# Placa_ATMEL_2019_v2_4.net
KiCad netlist of a schematic drawn in EAGLE
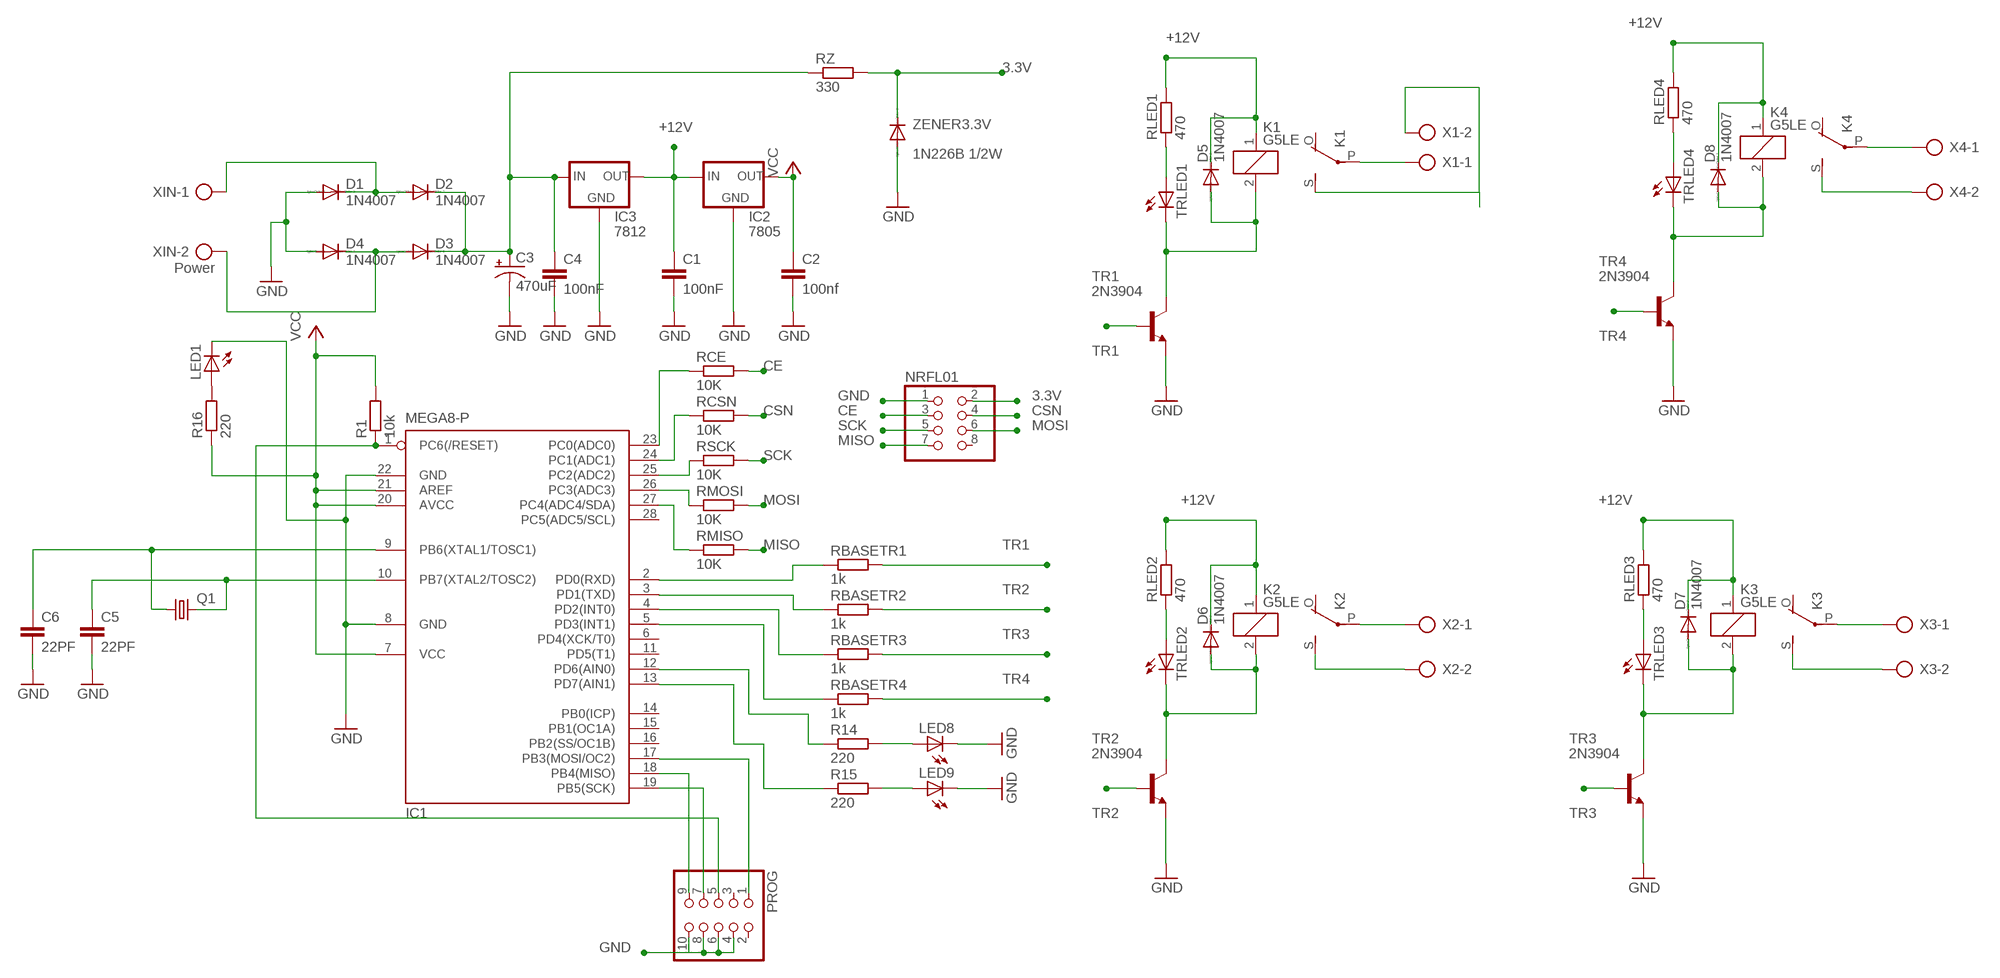
[diagram p0: schematic, sheet 1]

(export (version "E")
  (design (tool "Eeschema 10.0.6"))
  (components
    (comp (ref "C1")
      (value "100nF")
      (footprint "eagle-import:C050-025X075")
      (libsource (lib "eagle-import") (part "C-EU050-025X075"))
    )
    (comp (ref "C2")
      (value "100nf")
      (footprint "eagle-import:C050-025X075")
      (libsource (lib "eagle-import") (part "C-EU050-025X075"))
    )
    (comp (ref "C3")
      (value "470uF")
      (footprint "eagle-import:E7,5-16")
      (libsource (lib "eagle-import") (part "CPOL-USE7.5-16"))
    )
    (comp (ref "C4")
      (value "100nF")
      (footprint "eagle-import:C050-025X075")
      (libsource (lib "eagle-import") (part "C-EU050-025X075"))
    )
    (comp (ref "C5")
      (value "22PF")
      (footprint "eagle-import:C050-024X044")
      (libsource (lib "eagle-import") (part "C-EU050-024X044"))
    )
    (comp (ref "C6")
      (value "22PF")
      (footprint "eagle-import:C050-024X044")
      (libsource (lib "eagle-import") (part "C-EU050-024X044"))
    )
    (comp (ref "D1")
      (value "1N4007")
      (footprint "eagle-import:DO41-10")
      (libsource (lib "eagle-import") (part "1N4004"))
    )
    (comp (ref "D2")
      (value "1N4007")
      (footprint "eagle-import:DO41-10")
      (libsource (lib "eagle-import") (part "1N4004"))
    )
    (comp (ref "D3")
      (value "1N4007")
      (footprint "eagle-import:DO41-10")
      (libsource (lib "eagle-import") (part "1N4004"))
    )
    (comp (ref "D4")
      (value "1N4007")
      (footprint "eagle-import:DO41-10")
      (libsource (lib "eagle-import") (part "1N4004"))
    )
    (comp (ref "D5")
      (value "1N4007")
      (footprint "eagle-import:DO41-10")
      (libsource (lib "eagle-import") (part "1N4004"))
    )
    (comp (ref "D6")
      (value "1N4007")
      (footprint "eagle-import:DO41-10")
      (libsource (lib "eagle-import") (part "1N4004"))
    )
    (comp (ref "D7")
      (value "1N4007")
      (footprint "eagle-import:DO41-10")
      (libsource (lib "eagle-import") (part "1N4004"))
    )
    (comp (ref "D8")
      (value "1N4007")
      (footprint "eagle-import:DO41-10")
      (libsource (lib "eagle-import") (part "1N4004"))
    )
    (comp (ref "IC1")
      (value "MEGA8-P")
      (footprint "eagle-import:DIL28-3")
      (libsource (lib "eagle-import") (part "MEGA8-P"))
    )
    (comp (ref "IC2")
      (value "7805")
      (footprint "eagle-import:78XXL")
      (libsource (lib "eagle-import") (part "78XXL"))
    )
    (comp (ref "IC3")
      (value "7812")
      (footprint "eagle-import:78XXL")
      (libsource (lib "eagle-import") (part "78XXL"))
    )
    (comp (ref "K1")
      (value "G5LE")
      (footprint "eagle-import:G5LE")
      (libsource (lib "eagle-import") (part "G5LE"))
    )
    (comp (ref "K2")
      (value "G5LE")
      (footprint "eagle-import:G5LE")
      (libsource (lib "eagle-import") (part "G5LE"))
    )
    (comp (ref "K3")
      (value "G5LE")
      (footprint "eagle-import:G5LE")
      (libsource (lib "eagle-import") (part "G5LE"))
    )
    (comp (ref "K4")
      (value "G5LE")
      (footprint "eagle-import:G5LE")
      (libsource (lib "eagle-import") (part "G5LE"))
    )
    (comp (ref "LED1")
      (value "LED5MM")
      (footprint "eagle-import:LED5MM")
      (libsource (lib "eagle-import") (part "LED5MM"))
    )
    (comp (ref "LED8")
      (value "LED5MM")
      (footprint "eagle-import:LED5MM")
      (libsource (lib "eagle-import") (part "LED5MM"))
    )
    (comp (ref "LED9")
      (value "LED5MM")
      (footprint "eagle-import:LED5MM")
      (libsource (lib "eagle-import") (part "LED5MM"))
    )
    (comp (ref "NRFL01")
      (value "PINHD-2X4")
      (footprint "eagle-import:2X04")
      (libsource (lib "eagle-import") (part "PINHD-2X4"))
    )
    (comp (ref "PROG")
      (value "PINHD-2X5")
      (footprint "eagle-import:2X05")
      (libsource (lib "eagle-import") (part "PINHD-2X5"))
    )
    (comp (ref "Q1")
      (value "CRYSTALHC49S")
      (footprint "eagle-import:HC49_S")
      (libsource (lib "eagle-import") (part "CRYSTALHC49S"))
    )
    (comp (ref "R1")
      (value "10k")
      (footprint "eagle-import:0207_10")
      (libsource (lib "eagle-import") (part "R-EU_0207/10"))
    )
    (comp (ref "R14")
      (value "220")
      (footprint "eagle-import:0207_10")
      (libsource (lib "eagle-import") (part "R-EU_0207/10"))
    )
    (comp (ref "R15")
      (value "220")
      (footprint "eagle-import:0207_10")
      (libsource (lib "eagle-import") (part "R-EU_0207/10"))
    )
    (comp (ref "R16")
      (value "220")
      (footprint "eagle-import:0309_10")
      (libsource (lib "eagle-import") (part "R-EU_0309/10"))
    )
    (comp (ref "RBASETR1")
      (value "1k")
      (footprint "eagle-import:0207_10")
      (libsource (lib "eagle-import") (part "R-EU_0207/10"))
    )
    (comp (ref "RBASETR2")
      (value "1k")
      (footprint "eagle-import:0207_10")
      (libsource (lib "eagle-import") (part "R-EU_0207/10"))
    )
    (comp (ref "RBASETR3")
      (value "1k")
      (footprint "eagle-import:0204_7")
      (libsource (lib "eagle-import") (part "R-EU_0204/7"))
    )
    (comp (ref "RBASETR4")
      (value "1k")
      (footprint "eagle-import:0207_15")
      (libsource (lib "eagle-import") (part "R-EU_0207/15"))
    )
    (comp (ref "RCE")
      (value "10K")
      (footprint "eagle-import:0207_10")
      (libsource (lib "eagle-import") (part "R-EU_0207/10"))
    )
    (comp (ref "RCSN")
      (value "10K")
      (footprint "eagle-import:0207_10")
      (libsource (lib "eagle-import") (part "R-EU_0207/10"))
    )
    (comp (ref "RLED1")
      (value "470")
      (footprint "eagle-import:0207_10")
      (libsource (lib "eagle-import") (part "R-EU_0207/10"))
    )
    (comp (ref "RLED2")
      (value "470")
      (footprint "eagle-import:0207_10")
      (libsource (lib "eagle-import") (part "R-EU_0207/10"))
    )
    (comp (ref "RLED3")
      (value "470")
      (footprint "eagle-import:0207_10")
      (libsource (lib "eagle-import") (part "R-EU_0207/10"))
    )
    (comp (ref "RLED4")
      (value "470")
      (footprint "eagle-import:0207_10")
      (libsource (lib "eagle-import") (part "R-EU_0207/10"))
    )
    (comp (ref "RMISO")
      (value "10K")
      (footprint "eagle-import:0207_10")
      (libsource (lib "eagle-import") (part "R-EU_0207/10"))
    )
    (comp (ref "RMOSI")
      (value "10K")
      (footprint "eagle-import:0207_10")
      (libsource (lib "eagle-import") (part "R-EU_0207/10"))
    )
    (comp (ref "RSCK")
      (value "10K")
      (footprint "eagle-import:0207_10")
      (libsource (lib "eagle-import") (part "R-EU_0207/10"))
    )
    (comp (ref "RZ")
      (value "330")
      (footprint "eagle-import:0207_10")
      (libsource (lib "eagle-import") (part "R-EU_0207/10"))
    )
    (comp (ref "TR1")
      (value "2N3904")
      (footprint "eagle-import:TO92")
      (libsource (lib "eagle-import") (part "2N3904"))
    )
    (comp (ref "TR2")
      (value "2N3904")
      (footprint "eagle-import:TO92")
      (libsource (lib "eagle-import") (part "2N3904"))
    )
    (comp (ref "TR3")
      (value "2N3904")
      (footprint "eagle-import:TO92")
      (libsource (lib "eagle-import") (part "2N3904"))
    )
    (comp (ref "TR4")
      (value "2N3904")
      (footprint "eagle-import:TO92")
      (libsource (lib "eagle-import") (part "2N3904"))
    )
    (comp (ref "TRLED1")
      (value "LED5MM")
      (footprint "eagle-import:LED5MM")
      (libsource (lib "eagle-import") (part "LED5MM"))
    )
    (comp (ref "TRLED2")
      (value "LED5MM")
      (footprint "eagle-import:LED5MM")
      (libsource (lib "eagle-import") (part "LED5MM"))
    )
    (comp (ref "TRLED3")
      (value "LED5MM")
      (footprint "eagle-import:LED5MM")
      (libsource (lib "eagle-import") (part "LED5MM"))
    )
    (comp (ref "TRLED4")
      (value "LED5MM")
      (footprint "eagle-import:LED5MM")
      (libsource (lib "eagle-import") (part "LED5MM"))
    )
    (comp (ref "X1")
      (value "AK300/2")
      (footprint "eagle-import:AK300_2")
      (libsource (lib "eagle-import") (part "AK300/2"))
    )
    (comp (ref "X2")
      (value "AK300/2")
      (footprint "eagle-import:AK300_2")
      (libsource (lib "eagle-import") (part "AK300/2"))
    )
    (comp (ref "X3")
      (value "AK300/2")
      (footprint "eagle-import:AK300_2")
      (libsource (lib "eagle-import") (part "AK300/2"))
    )
    (comp (ref "X4")
      (value "AK300/2")
      (footprint "eagle-import:AK300_2")
      (libsource (lib "eagle-import") (part "AK300/2"))
    )
    (comp (ref "XIN")
      (value "Power")
      (footprint "eagle-import:AK500_2")
      (libsource (lib "eagle-import") (part "AK500/2"))
    )
    (comp (ref "ZENER3.3V")
      (value "1N226B 1/2W")
      (footprint "eagle-import:DO35-10")
      (libsource (lib "eagle-import") (part "1N4148DO35-10"))
    )
  )
  (nets
    (net (code "1") (name "/+12V") (class "Default")
      (node (ref "C1") (pin "1") (pinfunction "1_1") (pintype "passive"))
      (node (ref "D5") (pin "C") (pinfunction "C_C") (pintype "passive"))
      (node (ref "D6") (pin "C") (pinfunction "C_C") (pintype "passive"))
      (node (ref "D7") (pin "C") (pinfunction "C_C") (pintype "passive"))
      (node (ref "D8") (pin "C") (pinfunction "C_C") (pintype "passive"))
      (node (ref "IC2") (pin "IN") (pinfunction "IN_IN") (pintype "input"))
      (node (ref "IC3") (pin "OUT") (pinfunction "OUT_OUT") (pintype "passive"))
      (node (ref "K1") (pin "1") (pinfunction "1_1") (pintype "passive"))
      (node (ref "K2") (pin "1") (pinfunction "1_1") (pintype "passive"))
      (node (ref "K3") (pin "1") (pinfunction "1_1") (pintype "passive"))
      (node (ref "K4") (pin "1") (pinfunction "1_1") (pintype "passive"))
      (node (ref "RLED1") (pin "2") (pinfunction "2_2") (pintype "passive"))
      (node (ref "RLED2") (pin "2") (pinfunction "2_2") (pintype "passive"))
      (node (ref "RLED3") (pin "2") (pinfunction "2_2") (pintype "passive"))
      (node (ref "RLED4") (pin "2") (pinfunction "2_2") (pintype "passive"))
    )
    (net (code "2") (name "/3.3V") (class "Default")
      (node (ref "NRFL01") (pin "2") (pinfunction "2_2") (pintype "passive"))
      (node (ref "RZ") (pin "2") (pinfunction "2_2") (pintype "passive"))
      (node (ref "ZENER3.3V") (pin "C") (pinfunction "C_C") (pintype "passive"))
    )
    (net (code "3") (name "/CE") (class "Default")
      (node (ref "NRFL01") (pin "3") (pinfunction "3_3") (pintype "passive"))
      (node (ref "RCE") (pin "2") (pinfunction "2_2") (pintype "passive"))
    )
    (net (code "4") (name "/CSN") (class "Default")
      (node (ref "NRFL01") (pin "4") (pinfunction "4_4") (pintype "passive"))
      (node (ref "RCSN") (pin "2") (pinfunction "2_2") (pintype "passive"))
    )
    (net (code "5") (name "/MISO") (class "Default")
      (node (ref "NRFL01") (pin "7") (pinfunction "7_7") (pintype "passive"))
      (node (ref "RMISO") (pin "2") (pinfunction "2_2") (pintype "passive"))
    )
    (net (code "6") (name "/MOSI") (class "Default")
      (node (ref "NRFL01") (pin "6") (pinfunction "6_6") (pintype "passive"))
      (node (ref "RMOSI") (pin "2") (pinfunction "2_2") (pintype "passive"))
    )
    (net (code "7") (name "/SCK") (class "Default")
      (node (ref "NRFL01") (pin "5") (pinfunction "5_5") (pintype "passive"))
      (node (ref "RSCK") (pin "2") (pinfunction "2_2") (pintype "passive"))
    )
    (net (code "8") (name "/TR1") (class "Default")
      (node (ref "RBASETR1") (pin "2") (pinfunction "2_2") (pintype "passive"))
      (node (ref "TR1") (pin "2") (pinfunction "B_2") (pintype "passive"))
    )
    (net (code "9") (name "/TR2") (class "Default")
      (node (ref "RBASETR2") (pin "2") (pinfunction "2_2") (pintype "passive"))
      (node (ref "TR2") (pin "2") (pinfunction "B_2") (pintype "passive"))
    )
    (net (code "10") (name "/TR3") (class "Default")
      (node (ref "RBASETR3") (pin "2") (pinfunction "2_2") (pintype "passive"))
      (node (ref "TR3") (pin "2") (pinfunction "B_2") (pintype "passive"))
    )
    (net (code "11") (name "/TR4") (class "Default")
      (node (ref "RBASETR4") (pin "2") (pinfunction "2_2") (pintype "passive"))
      (node (ref "TR4") (pin "2") (pinfunction "B_2") (pintype "passive"))
    )
    (net (code "12") (name "GND") (class "Default")
      (node (ref "C1") (pin "2") (pinfunction "2_2") (pintype "passive"))
      (node (ref "C2") (pin "2") (pinfunction "2_2") (pintype "passive"))
      (node (ref "C3") (pin "-") (pinfunction "-_-") (pintype "passive"))
      (node (ref "C4") (pin "2") (pinfunction "2_2") (pintype "passive"))
      (node (ref "C5") (pin "2") (pinfunction "2_2") (pintype "passive"))
      (node (ref "C6") (pin "2") (pinfunction "2_2") (pintype "passive"))
      (node (ref "D1") (pin "A") (pinfunction "A_A") (pintype "passive"))
      (node (ref "D4") (pin "A") (pinfunction "A_A") (pintype "passive"))
      (node (ref "IC1") (pin "22") (pinfunction "GND_22") (pintype "power_in"))
      (node (ref "IC1") (pin "8") (pinfunction "GND_8") (pintype "power_in"))
      (node (ref "IC2") (pin "GND") (pinfunction "GND_GND") (pintype "input"))
      (node (ref "IC3") (pin "GND") (pinfunction "GND_GND") (pintype "input"))
      (node (ref "LED1") (pin "K") (pinfunction "C_K") (pintype "passive"))
      (node (ref "LED8") (pin "K") (pinfunction "C_K") (pintype "passive"))
      (node (ref "LED9") (pin "K") (pinfunction "C_K") (pintype "passive"))
      (node (ref "NRFL01") (pin "1") (pinfunction "1_1") (pintype "passive"))
      (node (ref "PROG") (pin "10") (pinfunction "10_10") (pintype "passive"))
      (node (ref "PROG") (pin "4") (pinfunction "4_4") (pintype "passive"))
      (node (ref "PROG") (pin "6") (pinfunction "6_6") (pintype "passive"))
      (node (ref "PROG") (pin "8") (pinfunction "8_8") (pintype "passive"))
      (node (ref "TR1") (pin "3") (pinfunction "E_3") (pintype "passive"))
      (node (ref "TR2") (pin "3") (pinfunction "E_3") (pintype "passive"))
      (node (ref "TR3") (pin "3") (pinfunction "E_3") (pintype "passive"))
      (node (ref "TR4") (pin "3") (pinfunction "E_3") (pintype "passive"))
      (node (ref "ZENER3.3V") (pin "A") (pinfunction "A_A") (pintype "passive"))
    )
    (net (code "13") (name "Net-(C3-Pad+)") (class "Default")
      (node (ref "C3") (pin "+") (pinfunction "+_+") (pintype "passive"))
      (node (ref "C4") (pin "1") (pinfunction "1_1") (pintype "passive"))
      (node (ref "D2") (pin "C") (pinfunction "C_C") (pintype "passive"))
      (node (ref "D3") (pin "C") (pinfunction "C_C") (pintype "passive"))
      (node (ref "IC3") (pin "IN") (pinfunction "IN_IN") (pintype "input"))
      (node (ref "RZ") (pin "1") (pinfunction "1_1") (pintype "passive"))
    )
    (net (code "14") (name "Net-(IC1-PB3(MOSI{slash}OC2))") (class "Default")
      (node (ref "IC1") (pin "17") (pinfunction "PB3(MOSI/OC2)_17") (pintype "bidirectional"))
      (node (ref "PROG") (pin "1") (pinfunction "1_1") (pintype "passive"))
    )
    (net (code "15") (name "Net-(IC1-PB4(MISO))") (class "Default")
      (node (ref "IC1") (pin "18") (pinfunction "PB4(MISO)_18") (pintype "bidirectional"))
      (node (ref "PROG") (pin "9") (pinfunction "9_9") (pintype "passive"))
    )
    (net (code "16") (name "Net-(IC1-PB5(SCK))") (class "Default")
      (node (ref "IC1") (pin "19") (pinfunction "PB5(SCK)_19") (pintype "bidirectional"))
      (node (ref "PROG") (pin "7") (pinfunction "7_7") (pintype "passive"))
    )
    (net (code "17") (name "Net-(IC1-PB6(XTAL1{slash}TOSC1))") (class "Default")
      (node (ref "C6") (pin "1") (pinfunction "1_1") (pintype "passive"))
      (node (ref "IC1") (pin "9") (pinfunction "PB6(XTAL1/TOSC1)_9") (pintype "bidirectional"))
      (node (ref "Q1") (pin "1") (pinfunction "1_1") (pintype "passive"))
    )
    (net (code "18") (name "Net-(IC1-PB7(XTAL2{slash}TOSC2))") (class "Default")
      (node (ref "C5") (pin "1") (pinfunction "1_1") (pintype "passive"))
      (node (ref "IC1") (pin "10") (pinfunction "PB7(XTAL2/TOSC2)_10") (pintype "bidirectional"))
      (node (ref "Q1") (pin "2") (pinfunction "2_2") (pintype "passive"))
    )
    (net (code "19") (name "Net-(IC1-PC0(ADC0))") (class "Default")
      (node (ref "IC1") (pin "23") (pinfunction "PC0(ADC0)_23") (pintype "bidirectional"))
      (node (ref "RCE") (pin "1") (pinfunction "1_1") (pintype "passive"))
    )
    (net (code "20") (name "Net-(IC1-PC1(ADC1))") (class "Default")
      (node (ref "IC1") (pin "24") (pinfunction "PC1(ADC1)_24") (pintype "bidirectional"))
      (node (ref "RCSN") (pin "1") (pinfunction "1_1") (pintype "passive"))
    )
    (net (code "21") (name "Net-(IC1-PC2(ADC2))") (class "Default")
      (node (ref "IC1") (pin "25") (pinfunction "PC2(ADC2)_25") (pintype "bidirectional"))
      (node (ref "RSCK") (pin "1") (pinfunction "1_1") (pintype "passive"))
    )
    (net (code "22") (name "Net-(IC1-PC3(ADC3))") (class "Default")
      (node (ref "IC1") (pin "26") (pinfunction "PC3(ADC3)_26") (pintype "bidirectional"))
      (node (ref "RMOSI") (pin "1") (pinfunction "1_1") (pintype "passive"))
    )
    (net (code "23") (name "Net-(IC1-PC4(ADC4{slash}SDA))") (class "Default")
      (node (ref "IC1") (pin "27") (pinfunction "PC4(ADC4/SDA)_27") (pintype "bidirectional"))
      (node (ref "RMISO") (pin "1") (pinfunction "1_1") (pintype "passive"))
    )
    (net (code "24") (name "Net-(IC1-PC6({slash}RESET))") (class "Default")
      (node (ref "IC1") (pin "1") (pinfunction "PC6(/RESET)_1") (pintype "bidirectional"))
      (node (ref "PROG") (pin "5") (pinfunction "5_5") (pintype "passive"))
      (node (ref "R1") (pin "1") (pinfunction "1_1") (pintype "passive"))
    )
    (net (code "25") (name "Net-(IC1-PD0(RXD))") (class "Default")
      (node (ref "IC1") (pin "2") (pinfunction "PD0(RXD)_2") (pintype "bidirectional"))
      (node (ref "RBASETR1") (pin "1") (pinfunction "1_1") (pintype "passive"))
    )
    (net (code "26") (name "Net-(IC1-PD1(TXD))") (class "Default")
      (node (ref "IC1") (pin "3") (pinfunction "PD1(TXD)_3") (pintype "bidirectional"))
      (node (ref "RBASETR2") (pin "1") (pinfunction "1_1") (pintype "passive"))
    )
    (net (code "27") (name "Net-(IC1-PD2(INT0))") (class "Default")
      (node (ref "IC1") (pin "4") (pinfunction "PD2(INT0)_4") (pintype "bidirectional"))
      (node (ref "RBASETR3") (pin "1") (pinfunction "1_1") (pintype "passive"))
    )
    (net (code "28") (name "Net-(IC1-PD3(INT1))") (class "Default")
      (node (ref "IC1") (pin "5") (pinfunction "PD3(INT1)_5") (pintype "bidirectional"))
      (node (ref "RBASETR4") (pin "1") (pinfunction "1_1") (pintype "passive"))
    )
    (net (code "29") (name "Net-(IC1-PD6(AIN0))") (class "Default")
      (node (ref "IC1") (pin "12") (pinfunction "PD6(AIN0)_12") (pintype "bidirectional"))
      (node (ref "R14") (pin "1") (pinfunction "1_1") (pintype "passive"))
    )
    (net (code "30") (name "Net-(IC1-PD7(AIN1))") (class "Default")
      (node (ref "IC1") (pin "13") (pinfunction "PD7(AIN1)_13") (pintype "bidirectional"))
      (node (ref "R15") (pin "1") (pinfunction "1_1") (pintype "passive"))
    )
    (net (code "31") (name "Net-(LED1-PadA)") (class "Default")
      (node (ref "LED1") (pin "A") (pinfunction "A_A") (pintype "passive"))
      (node (ref "R16") (pin "2") (pinfunction "2_2") (pintype "passive"))
    )
    (net (code "32") (name "Net-(LED8-PadA)") (class "Default")
      (node (ref "LED8") (pin "A") (pinfunction "A_A") (pintype "passive"))
      (node (ref "R14") (pin "2") (pinfunction "2_2") (pintype "passive"))
    )
    (net (code "33") (name "Net-(LED9-PadA)") (class "Default")
      (node (ref "LED9") (pin "A") (pinfunction "A_A") (pintype "passive"))
      (node (ref "R15") (pin "2") (pinfunction "2_2") (pintype "passive"))
    )
    (net (code "34") (name "Net-(RLED1-Pad1)") (class "Default")
      (node (ref "RLED1") (pin "1") (pinfunction "1_1") (pintype "passive"))
      (node (ref "TRLED1") (pin "A") (pinfunction "A_A") (pintype "passive"))
    )
    (net (code "35") (name "Net-(RLED2-Pad1)") (class "Default")
      (node (ref "RLED2") (pin "1") (pinfunction "1_1") (pintype "passive"))
      (node (ref "TRLED2") (pin "A") (pinfunction "A_A") (pintype "passive"))
    )
    (net (code "36") (name "Net-(RLED3-Pad1)") (class "Default")
      (node (ref "RLED3") (pin "1") (pinfunction "1_1") (pintype "passive"))
      (node (ref "TRLED3") (pin "A") (pinfunction "A_A") (pintype "passive"))
    )
    (net (code "37") (name "Net-(RLED4-Pad1)") (class "Default")
      (node (ref "RLED4") (pin "1") (pinfunction "1_1") (pintype "passive"))
      (node (ref "TRLED4") (pin "A") (pinfunction "A_A") (pintype "passive"))
    )
    (net (code "38") (name "Net-(TR1-C)") (class "Default")
      (node (ref "D5") (pin "A") (pinfunction "A_A") (pintype "passive"))
      (node (ref "K1") (pin "2") (pinfunction "2_2") (pintype "passive"))
      (node (ref "TR1") (pin "1") (pinfunction "C_1") (pintype "passive"))
      (node (ref "TRLED1") (pin "K") (pinfunction "C_K") (pintype "passive"))
    )
    (net (code "39") (name "Net-(TR2-C)") (class "Default")
      (node (ref "D6") (pin "A") (pinfunction "A_A") (pintype "passive"))
      (node (ref "K2") (pin "2") (pinfunction "2_2") (pintype "passive"))
      (node (ref "TR2") (pin "1") (pinfunction "C_1") (pintype "passive"))
      (node (ref "TRLED2") (pin "K") (pinfunction "C_K") (pintype "passive"))
    )
    (net (code "40") (name "Net-(TR3-C)") (class "Default")
      (node (ref "D7") (pin "A") (pinfunction "A_A") (pintype "passive"))
      (node (ref "K3") (pin "2") (pinfunction "2_2") (pintype "passive"))
      (node (ref "TR3") (pin "1") (pinfunction "C_1") (pintype "passive"))
      (node (ref "TRLED3") (pin "K") (pinfunction "C_K") (pintype "passive"))
    )
    (net (code "41") (name "Net-(TR4-C)") (class "Default")
      (node (ref "D8") (pin "A") (pinfunction "A_A") (pintype "passive"))
      (node (ref "K4") (pin "2") (pinfunction "2_2") (pintype "passive"))
      (node (ref "TR4") (pin "1") (pinfunction "C_1") (pintype "passive"))
      (node (ref "TRLED4") (pin "K") (pinfunction "C_K") (pintype "passive"))
    )
    (net (code "42") (name "Net-(X1A-KL)") (class "Default")
      (node (ref "K1") (pin "P") (pinfunction "P_P") (pintype "passive"))
      (node (ref "X1") (pin "1") (pinfunction "KL_1") (pintype "passive"))
    )
    (net (code "43") (name "Net-(X1B-KL)") (class "Default")
      (node (ref "K1") (pin "S") (pinfunction "S_S") (pintype "passive"))
      (node (ref "X1") (pin "2") (pinfunction "KL_2") (pintype "passive"))
    )
    (net (code "44") (name "Net-(X2A-KL)") (class "Default")
      (node (ref "K2") (pin "P") (pinfunction "P_P") (pintype "passive"))
      (node (ref "X2") (pin "1") (pinfunction "KL_1") (pintype "passive"))
    )
    (net (code "45") (name "Net-(X2B-KL)") (class "Default")
      (node (ref "K2") (pin "S") (pinfunction "S_S") (pintype "passive"))
      (node (ref "X2") (pin "2") (pinfunction "KL_2") (pintype "passive"))
    )
    (net (code "46") (name "Net-(X3A-KL)") (class "Default")
      (node (ref "K3") (pin "P") (pinfunction "P_P") (pintype "passive"))
      (node (ref "X3") (pin "1") (pinfunction "KL_1") (pintype "passive"))
    )
    (net (code "47") (name "Net-(X3B-KL)") (class "Default")
      (node (ref "K3") (pin "S") (pinfunction "S_S") (pintype "passive"))
      (node (ref "X3") (pin "2") (pinfunction "KL_2") (pintype "passive"))
    )
    (net (code "48") (name "Net-(X4A-KL)") (class "Default")
      (node (ref "K4") (pin "P") (pinfunction "P_P") (pintype "passive"))
      (node (ref "X4") (pin "1") (pinfunction "KL_1") (pintype "passive"))
    )
    (net (code "49") (name "Net-(X4B-KL)") (class "Default")
      (node (ref "K4") (pin "S") (pinfunction "S_S") (pintype "passive"))
      (node (ref "X4") (pin "2") (pinfunction "KL_2") (pintype "passive"))
    )
    (net (code "50") (name "Net-(XINA-KL)") (class "Default")
      (node (ref "D1") (pin "C") (pinfunction "C_C") (pintype "passive"))
      (node (ref "D2") (pin "A") (pinfunction "A_A") (pintype "passive"))
      (node (ref "XIN") (pin "1") (pinfunction "KL_1") (pintype "passive"))
    )
    (net (code "51") (name "Net-(XINB-KL)") (class "Default")
      (node (ref "D3") (pin "A") (pinfunction "A_A") (pintype "passive"))
      (node (ref "D4") (pin "C") (pinfunction "C_C") (pintype "passive"))
      (node (ref "XIN") (pin "2") (pinfunction "KL_2") (pintype "passive"))
    )
    (net (code "52") (name "VCC") (class "Default")
      (node (ref "C2") (pin "1") (pinfunction "1_1") (pintype "passive"))
      (node (ref "IC1") (pin "20") (pinfunction "AVCC_20") (pintype "power_in"))
      (node (ref "IC1") (pin "21") (pinfunction "AREF_21") (pintype "passive"))
      (node (ref "IC1") (pin "7") (pinfunction "VCC_7") (pintype "power_in"))
      (node (ref "IC2") (pin "OUT") (pinfunction "OUT_OUT") (pintype "passive"))
      (node (ref "R1") (pin "2") (pinfunction "2_2") (pintype "passive"))
      (node (ref "R16") (pin "1") (pinfunction "1_1") (pintype "passive"))
    )
    (net (code "53") (name "unconnected-(IC1-PB0(ICP)-Pad14)") (class "Default")
      (node (ref "IC1") (pin "14") (pinfunction "PB0(ICP)_14") (pintype "bidirectional"))
    )
    (net (code "54") (name "unconnected-(IC1-PB1(OC1A)-Pad15)") (class "Default")
      (node (ref "IC1") (pin "15") (pinfunction "PB1(OC1A)_15") (pintype "bidirectional"))
    )
    (net (code "55") (name "unconnected-(IC1-PB2(SS{slash}OC1B)-Pad16)") (class "Default")
      (node (ref "IC1") (pin "16") (pinfunction "PB2(SS/OC1B)_16") (pintype "bidirectional"))
    )
    (net (code "56") (name "unconnected-(IC1-PC5(ADC5{slash}SCL)-Pad28)") (class "Default")
      (node (ref "IC1") (pin "28") (pinfunction "PC5(ADC5/SCL)_28") (pintype "bidirectional"))
    )
    (net (code "57") (name "unconnected-(IC1-PD4(XCK{slash}T0)-Pad6)") (class "Default")
      (node (ref "IC1") (pin "6") (pinfunction "PD4(XCK/T0)_6") (pintype "bidirectional"))
    )
    (net (code "58") (name "unconnected-(IC1-PD5(T1)-Pad11)") (class "Default")
      (node (ref "IC1") (pin "11") (pinfunction "PD5(T1)_11") (pintype "bidirectional"))
    )
    (net (code "59") (name "unconnected-(K1-PadO)") (class "Default")
      (node (ref "K1") (pin "O") (pinfunction "O_O") (pintype "passive"))
    )
    (net (code "60") (name "unconnected-(K2-PadO)") (class "Default")
      (node (ref "K2") (pin "O") (pinfunction "O_O") (pintype "passive"))
    )
    (net (code "61") (name "unconnected-(K3-PadO)") (class "Default")
      (node (ref "K3") (pin "O") (pinfunction "O_O") (pintype "passive"))
    )
    (net (code "62") (name "unconnected-(K4-PadO)") (class "Default")
      (node (ref "K4") (pin "O") (pinfunction "O_O") (pintype "passive"))
    )
    (net (code "63") (name "unconnected-(NRFL01-Pad8)") (class "Default")
      (node (ref "NRFL01") (pin "8") (pinfunction "8_8") (pintype "passive"))
    )
    (net (code "64") (name "unconnected-(PROG-Pad2)") (class "Default")
      (node (ref "PROG") (pin "2") (pinfunction "2_2") (pintype "passive"))
    )
    (net (code "65") (name "unconnected-(PROG-Pad3)") (class "Default")
      (node (ref "PROG") (pin "3") (pinfunction "3_3") (pintype "passive"))
    )
  )
)
